# easyeda_source.net
KiCad netlist of a schematic drawn in EasyEDA
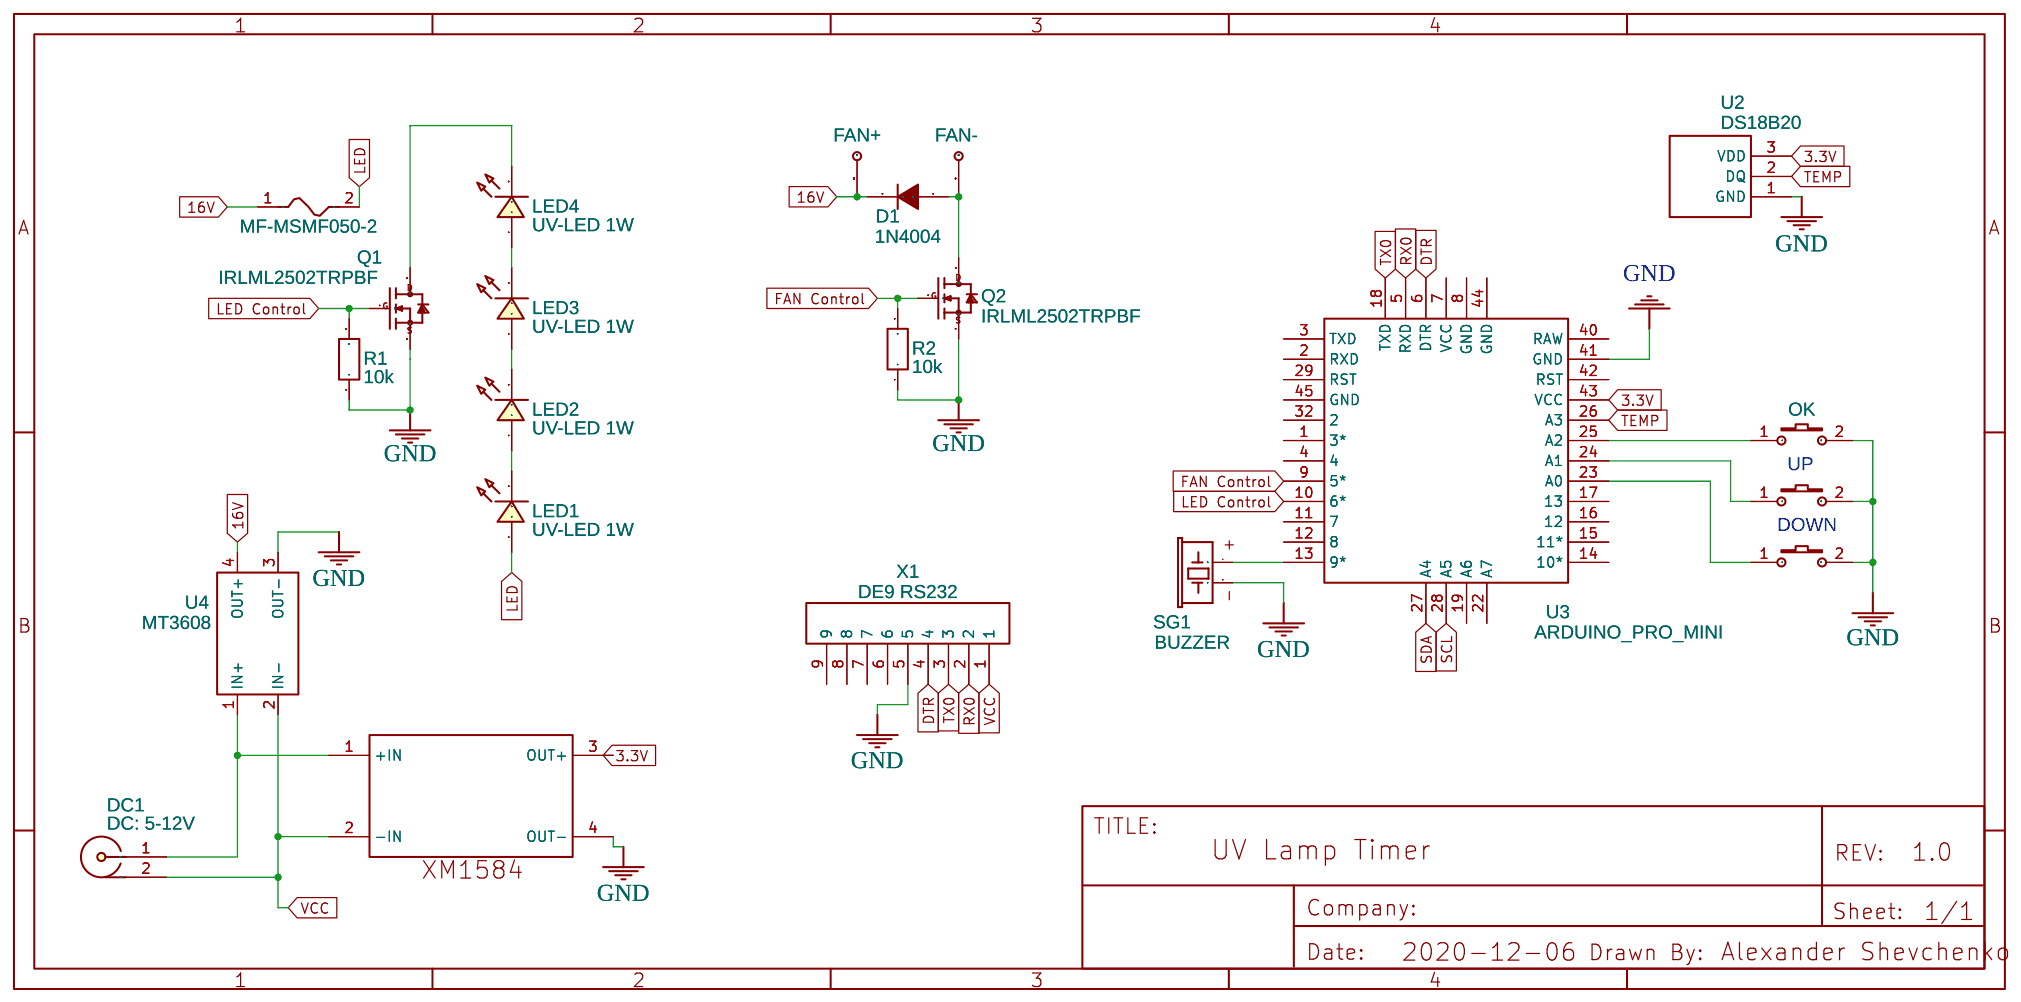
[diagram p0: schematic sheet]

(export (version "E")
  (design (tool "Eeschema 10.0.6"))
  (components
    (comp (ref "D1")
      (value "1N4004")
      (fields (field (name "BOM_Supplier Part") "C3058"))
      (libsource (lib "") (part "1N4004"))
    )
    (comp (ref "DC-DC") (value "XM1584") (libsource (lib "") (part "XM1584")))
    (comp (ref "DC1")
      (value "DC: 5-12V")
      (fields (field (name "BOM_Manufacturer Part") "DC005-2.0MM"))
      (libsource (lib "") (part "DC-input"))
    )
    (comp (ref "FAN+") (value "Pad") (libsource (lib "") (part "Pad")))
    (comp (ref "FAN-") (value "Pad") (libsource (lib "") (part "Pad_1")))
    (comp (ref "FUSE1")
      (value "MF-MSMF050-2")
      (fields (field (name "BOM_Supplier Part") "C17313"))
      (libsource (lib "") (part "FUSE MF-MSMF050-2"))
    )
    (comp (ref "KEY1")
      (value "+")
      (fields
        (field (name "BOM_Manufacturer Part") "K2-1107ST-A4SW-06")
        (field (name "BOM_Supplier Part") "C118141")
      )
      (libsource (lib "") (part "K2-3.6×6.1_SMD"))
    )
    (comp (ref "KEY5")
      (value "+")
      (fields
        (field (name "BOM_Manufacturer Part") "K2-1107ST-A4SW-06")
        (field (name "BOM_Supplier Part") "C118141")
      )
      (libsource (lib "") (part "K2-3.6×6.1_SMD"))
    )
    (comp (ref "KEY6")
      (value "OK")
      (fields
        (field (name "BOM_Manufacturer Part") "K2-1107ST-A4SW-06")
        (field (name "BOM_Supplier Part") "C118141")
      )
      (libsource (lib "") (part "K2-3.6×6.1_SMD"))
    )
    (comp (ref "LED1")
      (value "UV-LED 1W")
      (fields
        (field (name "BOM_Manufacturer Part") "19-217/R6C-AL1M2VY/3T")
        (field (name "BOM_Supplier Part") "C72044")
      )
      (libsource (lib "") (part "LED-0603_R"))
    )
    (comp (ref "LED2")
      (value "UV-LED 1W")
      (fields
        (field (name "BOM_Manufacturer Part") "19-217/R6C-AL1M2VY/3T")
        (field (name "BOM_Supplier Part") "C72044")
      )
      (libsource (lib "") (part "LED-0603_R"))
    )
    (comp (ref "LED3")
      (value "UV-LED 1W")
      (fields
        (field (name "BOM_Manufacturer Part") "19-217/R6C-AL1M2VY/3T")
        (field (name "BOM_Supplier Part") "C72044")
      )
      (libsource (lib "") (part "LED-0603_R"))
    )
    (comp (ref "LED4")
      (value "UV-LED 1W")
      (fields
        (field (name "BOM_Manufacturer Part") "19-217/R6C-AL1M2VY/3T")
        (field (name "BOM_Supplier Part") "C72044")
      )
      (libsource (lib "") (part "LED-0603_R"))
    )
    (comp (ref "Q1")
      (value "IRLML2502TRPBF")
      (fields (field (name "BOM_Supplier Part") "305030022"))
      (libsource (lib "") (part "IRLML2502TRPBF"))
    )
    (comp (ref "Q2")
      (value "IRLML2502TRPBF")
      (fields (field (name "BOM_Supplier Part") "305030022"))
      (libsource (lib "") (part "IRLML2502TRPBF"))
    )
    (comp (ref "R1") (value "10k") (libsource (lib "") (part "R_0201_EU")))
    (comp (ref "R2") (value "10k") (libsource (lib "") (part "R_0201_EU")))
    (comp (ref "SG1") (value "BUZZER") (libsource (lib "") (part "BUZZER")))
    (comp (ref "U2")
      (value "DS18B20")
      (fields (field (name "BOM_Manufacturer Part") "DS18B20+") (field (name "BOM_Supplier Part") "C9753"))
      (libsource (lib "") (part "DS18B20"))
    )
    (comp (ref "U3") (value "ARDUINO_PRO_MINI") (libsource (lib "") (part "ARDUINO_PRO_MINI")))
    (comp (ref "U4") (value "MT3608") (libsource (lib "") (part "MT3608 4-band module")))
    (comp (ref "X1") (value "DE9 RS232") (libsource (lib "") (part "DE9_TO_SIL_RS232")))
  )
  (nets
    (net (code "1") (name "3.3V") (class "Default")
      (node (ref "DC-DC") (pin "3") (pinfunction "OUT+_3") (pintype "unspecified"))
      (node (ref "U2") (pin "3") (pinfunction "VDD_3") (pintype "unspecified"))
      (node (ref "U3") (pin "43") (pinfunction "VCC_43") (pintype "unspecified"))
    )
    (net (code "2") (name "16V") (class "Default")
      (node (ref "D1") (pin "2") (pinfunction "K_2") (pintype "unspecified"))
      (node (ref "FAN+") (pin "P$1") (pinfunction "P$1_P$1") (pintype "unspecified"))
      (node (ref "FUSE1") (pin "1") (pinfunction "1_1") (pintype "unspecified"))
      (node (ref "U4") (pin "4") (pinfunction "OUT+_4") (pintype "passive"))
    )
    (net (code "3") (name "DTR") (class "Default")
      (node (ref "U3") (pin "6") (pinfunction "DTR_6") (pintype "unspecified"))
      (node (ref "X1") (pin "4") (pinfunction "4_4") (pintype "unspecified"))
    )
    (net (code "4") (name "FAN Control") (class "Default")
      (node (ref "Q2") (pin "1") (pinfunction "G_1") (pintype "unspecified"))
      (node (ref "R2") (pin "2") (pinfunction "2_2") (pintype "unspecified"))
      (node (ref "U3") (pin "9") (pinfunction "5*_9") (pintype "unspecified"))
    )
    (net (code "5") (name "GND") (class "Default")
      (node (ref "DC-DC") (pin "4") (pinfunction "OUT-_4") (pintype "unspecified"))
      (node (ref "KEY1") (pin "2") (pinfunction "2_2") (pintype "unspecified"))
      (node (ref "KEY5") (pin "2") (pinfunction "2_2") (pintype "unspecified"))
      (node (ref "KEY6") (pin "2") (pinfunction "2_2") (pintype "unspecified"))
      (node (ref "Q1") (pin "2") (pinfunction "S_2") (pintype "unspecified"))
      (node (ref "Q2") (pin "2") (pinfunction "S_2") (pintype "unspecified"))
      (node (ref "R1") (pin "1") (pinfunction "1_1") (pintype "unspecified"))
      (node (ref "R2") (pin "1") (pinfunction "1_1") (pintype "unspecified"))
      (node (ref "SG1") (pin "+") (pinfunction "1_+") (pintype "unspecified"))
      (node (ref "U2") (pin "1") (pinfunction "GND_1") (pintype "unspecified"))
      (node (ref "U3") (pin "41") (pinfunction "GND_41") (pintype "unspecified"))
      (node (ref "U4") (pin "3") (pinfunction "OUT-_3") (pintype "passive"))
      (node (ref "X1") (pin "5") (pinfunction "5_5") (pintype "unspecified"))
    )
    (net (code "6") (name "LED") (class "Default")
      (node (ref "FUSE1") (pin "2") (pinfunction "2_2") (pintype "unspecified"))
      (node (ref "LED1") (pin "1") (pinfunction "1_1") (pintype "unspecified"))
    )
    (net (code "7") (name "LED Control") (class "Default")
      (node (ref "Q1") (pin "1") (pinfunction "G_1") (pintype "unspecified"))
      (node (ref "R1") (pin "2") (pinfunction "2_2") (pintype "unspecified"))
      (node (ref "U3") (pin "10") (pinfunction "6*_10") (pintype "unspecified"))
    )
    (net (code "8") (name "Net-(D1-A)") (class "Default")
      (node (ref "D1") (pin "1") (pinfunction "A_1") (pintype "unspecified"))
      (node (ref "FAN-") (pin "P$1") (pinfunction "P$1_P$1") (pintype "unspecified"))
      (node (ref "Q2") (pin "3") (pinfunction "D_3") (pintype "unspecified"))
    )
    (net (code "9") (name "Net-(DC-DC-+IN)") (class "Default")
      (node (ref "DC-DC") (pin "1") (pinfunction "+IN_1") (pintype "unspecified"))
      (node (ref "DC1") (pin "1") (pinfunction "VCC_1") (pintype "input"))
      (node (ref "U4") (pin "1") (pinfunction "IN+_1") (pintype "passive"))
    )
    (net (code "10") (name "Net-(LED1-Pad2)") (class "Default")
      (node (ref "LED1") (pin "2") (pinfunction "2_2") (pintype "unspecified"))
      (node (ref "LED2") (pin "1") (pinfunction "1_1") (pintype "unspecified"))
    )
    (net (code "11") (name "Net-(LED2-Pad2)") (class "Default")
      (node (ref "LED2") (pin "2") (pinfunction "2_2") (pintype "unspecified"))
      (node (ref "LED3") (pin "1") (pinfunction "1_1") (pintype "unspecified"))
    )
    (net (code "12") (name "Net-(LED3-Pad2)") (class "Default")
      (node (ref "LED3") (pin "2") (pinfunction "2_2") (pintype "unspecified"))
      (node (ref "LED4") (pin "1") (pinfunction "1_1") (pintype "unspecified"))
    )
    (net (code "13") (name "Net-(Q1-D)") (class "Default")
      (node (ref "LED4") (pin "2") (pinfunction "2_2") (pintype "unspecified"))
      (node (ref "Q1") (pin "3") (pinfunction "D_3") (pintype "unspecified"))
    )
    (net (code "14") (name "Net-(SG1-2)") (class "Default")
      (node (ref "SG1") (pin "-") (pinfunction "2_-") (pintype "unspecified"))
      (node (ref "U3") (pin "13") (pinfunction "9*_13") (pintype "unspecified"))
    )
    (net (code "15") (name "Net-(U3-A0)") (class "Default")
      (node (ref "KEY5") (pin "1") (pinfunction "1_1") (pintype "unspecified"))
      (node (ref "U3") (pin "23") (pinfunction "A0_23") (pintype "unspecified"))
    )
    (net (code "16") (name "Net-(U3-A1)") (class "Default")
      (node (ref "KEY1") (pin "1") (pinfunction "1_1") (pintype "unspecified"))
      (node (ref "U3") (pin "24") (pinfunction "A1_24") (pintype "unspecified"))
    )
    (net (code "17") (name "Net-(U3-A2)") (class "Default")
      (node (ref "KEY6") (pin "1") (pinfunction "1_1") (pintype "unspecified"))
      (node (ref "U3") (pin "25") (pinfunction "A2_25") (pintype "unspecified"))
    )
    (net (code "18") (name "RX0") (class "Default")
      (node (ref "U3") (pin "5") (pinfunction "RXD_5") (pintype "unspecified"))
      (node (ref "X1") (pin "2") (pinfunction "2_2") (pintype "unspecified"))
    )
    (net (code "19") (name "SCL") (class "Default")
      (node (ref "U3") (pin "28") (pinfunction "A5_28") (pintype "unspecified"))
    )
    (net (code "20") (name "SDA") (class "Default")
      (node (ref "U3") (pin "27") (pinfunction "A4_27") (pintype "unspecified"))
    )
    (net (code "21") (name "TEMP") (class "Default")
      (node (ref "U2") (pin "2") (pinfunction "DQ_2") (pintype "unspecified"))
      (node (ref "U3") (pin "26") (pinfunction "A3_26") (pintype "unspecified"))
    )
    (net (code "22") (name "TX0") (class "Default")
      (node (ref "U3") (pin "18") (pinfunction "TXD_18") (pintype "unspecified"))
      (node (ref "X1") (pin "3") (pinfunction "3_3") (pintype "unspecified"))
    )
    (net (code "23") (name "VCC") (class "Default")
      (node (ref "DC-DC") (pin "2") (pinfunction "-IN_2") (pintype "unspecified"))
      (node (ref "DC1") (pin "2") (pinfunction "2_2") (pintype "input"))
      (node (ref "U4") (pin "2") (pinfunction "IN-_2") (pintype "passive"))
      (node (ref "X1") (pin "1") (pinfunction "1_1") (pintype "unspecified"))
    )
    (net (code "24") (name "unconnected-(U3-2-Pad32)") (class "Default")
      (node (ref "U3") (pin "32") (pinfunction "2_32") (pintype "unspecified"))
    )
    (net (code "25") (name "unconnected-(U3-3*-Pad1)") (class "Default")
      (node (ref "U3") (pin "1") (pinfunction "3*_1") (pintype "unspecified"))
    )
    (net (code "26") (name "unconnected-(U3-7-Pad11)") (class "Default")
      (node (ref "U3") (pin "11") (pinfunction "7_11") (pintype "unspecified"))
    )
    (net (code "27") (name "unconnected-(U3-8-Pad12)") (class "Default")
      (node (ref "U3") (pin "12") (pinfunction "8_12") (pintype "unspecified"))
    )
    (net (code "28") (name "unconnected-(U3-10*-Pad14)") (class "Default")
      (node (ref "U3") (pin "14") (pinfunction "10*_14") (pintype "unspecified"))
    )
    (net (code "29") (name "unconnected-(U3-11*-Pad15)") (class "Default")
      (node (ref "U3") (pin "15") (pinfunction "11*_15") (pintype "unspecified"))
    )
    (net (code "30") (name "unconnected-(U3-12-Pad16)") (class "Default")
      (node (ref "U3") (pin "16") (pinfunction "12_16") (pintype "unspecified"))
    )
    (net (code "31") (name "unconnected-(U3-13-Pad17)") (class "Default")
      (node (ref "U3") (pin "17") (pinfunction "13_17") (pintype "unspecified"))
    )
    (net (code "32") (name "unconnected-(U3-A6-Pad19)") (class "Default")
      (node (ref "U3") (pin "19") (pinfunction "A6_19") (pintype "unspecified"))
    )
    (net (code "33") (name "unconnected-(U3-A7-Pad22)") (class "Default")
      (node (ref "U3") (pin "22") (pinfunction "A7_22") (pintype "unspecified"))
    )
    (net (code "34") (name "unconnected-(U3-GND-Pad8)") (class "Default")
      (node (ref "U3") (pin "8") (pinfunction "GND_8") (pintype "unspecified"))
    )
    (net (code "35") (name "unconnected-(U3-GND-Pad44)") (class "Default")
      (node (ref "U3") (pin "44") (pinfunction "GND_44") (pintype "unspecified"))
    )
    (net (code "36") (name "unconnected-(U3-GND-Pad45)") (class "Default")
      (node (ref "U3") (pin "45") (pinfunction "GND_45") (pintype "unspecified"))
    )
    (net (code "37") (name "unconnected-(U3-Pad4)") (class "Default")
      (node (ref "U3") (pin "4") (pinfunction "4_4") (pintype "unspecified"))
    )
    (net (code "38") (name "unconnected-(U3-RAW-Pad40)") (class "Default")
      (node (ref "U3") (pin "40") (pinfunction "RAW_40") (pintype "unspecified"))
    )
    (net (code "39") (name "unconnected-(U3-RST-Pad29)") (class "Default")
      (node (ref "U3") (pin "29") (pinfunction "RST_29") (pintype "unspecified"))
    )
    (net (code "40") (name "unconnected-(U3-RST-Pad42)") (class "Default")
      (node (ref "U3") (pin "42") (pinfunction "RST_42") (pintype "unspecified"))
    )
    (net (code "41") (name "unconnected-(U3-RXD-Pad2)") (class "Default")
      (node (ref "U3") (pin "2") (pinfunction "RXD_2") (pintype "unspecified"))
    )
    (net (code "42") (name "unconnected-(U3-TXD-Pad3)") (class "Default")
      (node (ref "U3") (pin "3") (pinfunction "TXD_3") (pintype "unspecified"))
    )
    (net (code "43") (name "unconnected-(U3-VCC-Pad7)") (class "Default")
      (node (ref "U3") (pin "7") (pinfunction "VCC_7") (pintype "unspecified"))
    )
    (net (code "44") (name "unconnected-(X1-Pad6)") (class "Default")
      (node (ref "X1") (pin "6") (pinfunction "6_6") (pintype "unspecified"))
    )
    (net (code "45") (name "unconnected-(X1-Pad7)") (class "Default")
      (node (ref "X1") (pin "7") (pinfunction "7_7") (pintype "unspecified"))
    )
    (net (code "46") (name "unconnected-(X1-Pad8)") (class "Default")
      (node (ref "X1") (pin "8") (pinfunction "8_8") (pintype "unspecified"))
    )
    (net (code "47") (name "unconnected-(X1-Pad9)") (class "Default")
      (node (ref "X1") (pin "9") (pinfunction "9_9") (pintype "unspecified"))
    )
  )
)
